# UART-to-ESP32-WROOM_with_JTAG.net
KiCad netlist of a schematic drawn in EAGLE
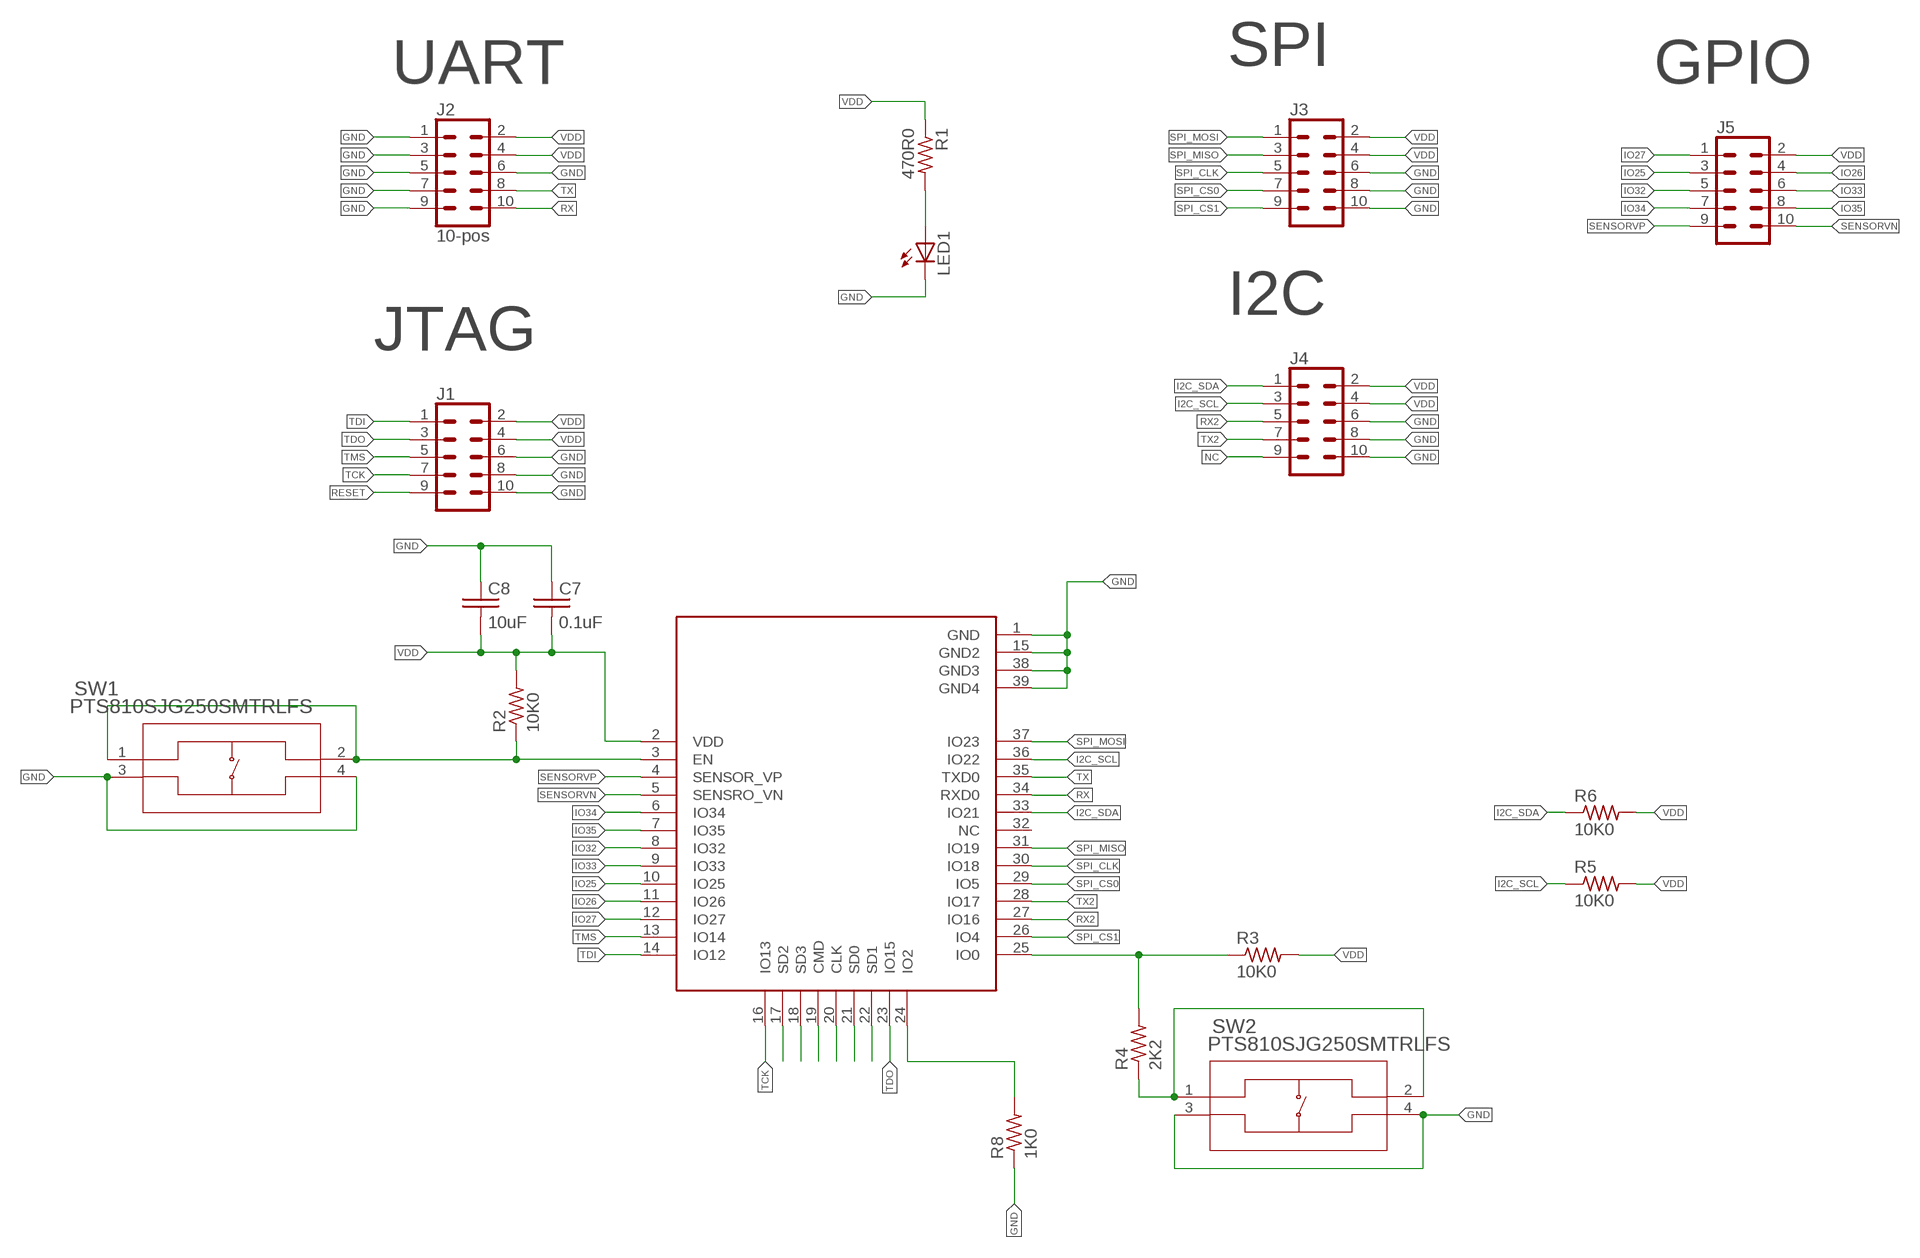
[diagram p0: schematic, sheet 1]

(export (version "E")
  (design (tool "Eeschema 10.0.6"))
  (components
    (comp (ref "C7")
      (value "0.1uF")
      (footprint "eagle-import:0402")
      (fields (field (name "PARTNO") "CL05F104ZO5NNNC"))
      (libsource (lib "eagle-import") (part "C_0402_0.1UF"))
    )
    (comp (ref "C8")
      (value "10uF")
      (footprint "eagle-import:0402")
      (fields (field (name "PARTNO") "CL05A106MP8NUB8"))
      (libsource (lib "eagle-import") (part "C_0402_10UF"))
    )
    (comp (ref "J1")
      (value "CONN_05X2PTH")
      (footprint "eagle-import:2X5")
      (libsource (lib "eagle-import") (part "CONN_05X2PTH"))
    )
    (comp (ref "J2")
      (value "10-pos")
      (footprint "eagle-import:2X5@1")
      (fields (field (name "PARTNO") "PH2RA-10-UA"))
      (libsource (lib "eagle-import") (part "CONN_05X2_RAPTH"))
    )
    (comp (ref "J3")
      (value "CONN_05X2PTH")
      (footprint "eagle-import:2X5")
      (libsource (lib "eagle-import") (part "CONN_05X2PTH"))
    )
    (comp (ref "J4")
      (value "CONN_05X2PTH")
      (footprint "eagle-import:2X5")
      (libsource (lib "eagle-import") (part "CONN_05X2PTH"))
    )
    (comp (ref "J5")
      (value "CONN_05X2PTH")
      (footprint "eagle-import:2X5")
      (libsource (lib "eagle-import") (part "CONN_05X2PTH"))
    )
    (comp (ref "LED1")
      (value "Green")
      (footprint "eagle-import:LED_0805_GREEN")
      (fields (field (name "PARTNO") "LG R971-KN-1"))
      (libsource (lib "eagle-import") (part "LED_0805_GREEN"))
    )
    (comp (ref "R1")
      (value "470R0")
      (footprint "eagle-import:0402")
      (fields (field (name "PARTNO") "RMCF0402JT470R"))
      (libsource (lib "eagle-import") (part "R_0402_470R0"))
    )
    (comp (ref "R2")
      (value "10K0")
      (footprint "eagle-import:0402")
      (fields (field (name "PARTNO") "RMCF0402JT10K0"))
      (libsource (lib "eagle-import") (part "R_0402_10K0"))
    )
    (comp (ref "R3")
      (value "10K0")
      (footprint "eagle-import:0402")
      (fields (field (name "PARTNO") "RMCF0402JT10K0"))
      (libsource (lib "eagle-import") (part "R_0402_10K0"))
    )
    (comp (ref "R4")
      (value "2K2")
      (footprint "eagle-import:0402")
      (fields (field (name "PARTNO") "RMCF0402JT2K20"))
      (libsource (lib "eagle-import") (part "R_0402_2K2"))
    )
    (comp (ref "R5")
      (value "10K0")
      (footprint "eagle-import:0402")
      (fields (field (name "PARTNO") "RMCF0402JT10K0"))
      (libsource (lib "eagle-import") (part "R_0402_10K0"))
    )
    (comp (ref "R6")
      (value "10K0")
      (footprint "eagle-import:0402")
      (fields (field (name "PARTNO") "RMCF0402JT10K0"))
      (libsource (lib "eagle-import") (part "R_0402_10K0"))
    )
    (comp (ref "R8")
      (value "1K0")
      (footprint "eagle-import:0402")
      (fields (field (name "PARTNO") "CRG0402J1K0"))
      (libsource (lib "eagle-import") (part "R_0402_1K0"))
    )
    (comp (ref "SW1")
      (value "PTS810SJG250SMTRLFS")
      (footprint "eagle-import:PTS810")
      (fields (field (name "COPYRIGHT") "Copyright (C) 2018 Accelerated Designs. All rights reserved"))
      (libsource (lib "eagle-import") (part "PTS810SJG250SMTRLFS"))
    )
    (comp (ref "SW2")
      (value "PTS810SJG250SMTRLFS")
      (footprint "eagle-import:PTS810")
      (fields (field (name "COPYRIGHT") "Copyright (C) 2018 Accelerated Designs. All rights reserved"))
      (libsource (lib "eagle-import") (part "PTS810SJG250SMTRLFS"))
    )
    (comp (ref "U2")
      (value "ESP32-WROOM-32D")
      (footprint "eagle-import:ESP32-WROOM-32D")
      (libsource (lib "eagle-import") (part "ESP32-WROOM-32D"))
    )
  )
  (nets
    (net (code "1") (name "GND") (class "Default")
      (node (ref "C7") (pin "P$1") (pinfunction "1_P$1") (pintype "passive"))
      (node (ref "C8") (pin "P$1") (pinfunction "1_P$1") (pintype "passive"))
      (node (ref "J1") (pin "10") (pinfunction "10_10") (pintype "passive"))
      (node (ref "J1") (pin "6") (pinfunction "6_6") (pintype "passive"))
      (node (ref "J1") (pin "8") (pinfunction "8_8") (pintype "passive"))
      (node (ref "J2") (pin "1") (pinfunction "1_1") (pintype "passive"))
      (node (ref "J2") (pin "3") (pinfunction "3_3") (pintype "passive"))
      (node (ref "J2") (pin "5") (pinfunction "5_5") (pintype "passive"))
      (node (ref "J2") (pin "6") (pinfunction "6_6") (pintype "passive"))
      (node (ref "J2") (pin "7") (pinfunction "7_7") (pintype "passive"))
      (node (ref "J2") (pin "9") (pinfunction "9_9") (pintype "passive"))
      (node (ref "J3") (pin "10") (pinfunction "10_10") (pintype "passive"))
      (node (ref "J3") (pin "6") (pinfunction "6_6") (pintype "passive"))
      (node (ref "J3") (pin "8") (pinfunction "8_8") (pintype "passive"))
      (node (ref "J4") (pin "10") (pinfunction "10_10") (pintype "passive"))
      (node (ref "J4") (pin "6") (pinfunction "6_6") (pintype "passive"))
      (node (ref "J4") (pin "8") (pinfunction "8_8") (pintype "passive"))
      (node (ref "LED1") (pin "C") (pinfunction "C_C") (pintype "passive"))
      (node (ref "R8") (pin "P$1") (pinfunction "1_P$1") (pintype "passive"))
      (node (ref "SW1") (pin "3") (pinfunction "3_3") (pintype "passive"))
      (node (ref "SW1") (pin "4") (pinfunction "4_4") (pintype "passive"))
      (node (ref "SW2") (pin "3") (pinfunction "3_3") (pintype "passive"))
      (node (ref "SW2") (pin "4") (pinfunction "4_4") (pintype "passive"))
      (node (ref "U2") (pin "1") (pinfunction "GND_1") (pintype "bidirectional"))
      (node (ref "U2") (pin "15") (pinfunction "GND2_15") (pintype "bidirectional"))
      (node (ref "U2") (pin "38") (pinfunction "GND3_38") (pintype "bidirectional"))
      (node (ref "U2") (pin "39") (pinfunction "GND4_39") (pintype "bidirectional"))
    )
    (net (code "2") (name "I2C_SCL") (class "Default")
      (node (ref "J4") (pin "3") (pinfunction "3_3") (pintype "passive"))
      (node (ref "R5") (pin "P$1") (pinfunction "1_P$1") (pintype "passive"))
      (node (ref "U2") (pin "36") (pinfunction "IO22_36") (pintype "bidirectional"))
    )
    (net (code "3") (name "I2C_SDA") (class "Default")
      (node (ref "J4") (pin "1") (pinfunction "1_1") (pintype "passive"))
      (node (ref "R6") (pin "P$1") (pinfunction "1_P$1") (pintype "passive"))
      (node (ref "U2") (pin "33") (pinfunction "IO21_33") (pintype "bidirectional"))
    )
    (net (code "4") (name "IO25") (class "Default")
      (node (ref "J5") (pin "3") (pinfunction "3_3") (pintype "passive"))
      (node (ref "U2") (pin "10") (pinfunction "IO25_10") (pintype "bidirectional"))
    )
    (net (code "5") (name "IO26") (class "Default")
      (node (ref "J5") (pin "4") (pinfunction "4_4") (pintype "passive"))
      (node (ref "U2") (pin "11") (pinfunction "IO26_11") (pintype "bidirectional"))
    )
    (net (code "6") (name "IO27") (class "Default")
      (node (ref "J5") (pin "1") (pinfunction "1_1") (pintype "passive"))
      (node (ref "U2") (pin "12") (pinfunction "IO27_12") (pintype "bidirectional"))
    )
    (net (code "7") (name "IO32") (class "Default")
      (node (ref "J5") (pin "5") (pinfunction "5_5") (pintype "passive"))
      (node (ref "U2") (pin "8") (pinfunction "IO32_8") (pintype "bidirectional"))
    )
    (net (code "8") (name "IO33") (class "Default")
      (node (ref "J5") (pin "6") (pinfunction "6_6") (pintype "passive"))
      (node (ref "U2") (pin "9") (pinfunction "IO33_9") (pintype "bidirectional"))
    )
    (net (code "9") (name "IO34") (class "Default")
      (node (ref "J5") (pin "7") (pinfunction "7_7") (pintype "passive"))
      (node (ref "U2") (pin "6") (pinfunction "IO34_6") (pintype "bidirectional"))
    )
    (net (code "10") (name "IO35") (class "Default")
      (node (ref "J5") (pin "8") (pinfunction "8_8") (pintype "passive"))
      (node (ref "U2") (pin "7") (pinfunction "IO35_7") (pintype "bidirectional"))
    )
    (net (code "11") (name "NC") (class "Default")
      (node (ref "J4") (pin "9") (pinfunction "9_9") (pintype "passive"))
    )
    (net (code "12") (name "Net-(R1-2)") (class "Default")
      (node (ref "LED1") (pin "A") (pinfunction "A_A") (pintype "passive"))
      (node (ref "R1") (pin "P$2") (pinfunction "2_P$2") (pintype "passive"))
    )
    (net (code "13") (name "Net-(R2-1)") (class "Default")
      (node (ref "R2") (pin "P$1") (pinfunction "1_P$1") (pintype "passive"))
      (node (ref "SW1") (pin "1") (pinfunction "1_1") (pintype "passive"))
      (node (ref "SW1") (pin "2") (pinfunction "2_2") (pintype "passive"))
      (node (ref "U2") (pin "3") (pinfunction "EN_3") (pintype "bidirectional"))
    )
    (net (code "14") (name "Net-(R3-1)") (class "Default")
      (node (ref "R3") (pin "P$1") (pinfunction "1_P$1") (pintype "passive"))
      (node (ref "R4") (pin "P$2") (pinfunction "2_P$2") (pintype "passive"))
      (node (ref "U2") (pin "25") (pinfunction "IO0_25") (pintype "bidirectional"))
    )
    (net (code "15") (name "Net-(R4-1)") (class "Default")
      (node (ref "R4") (pin "P$1") (pinfunction "1_P$1") (pintype "passive"))
      (node (ref "SW2") (pin "1") (pinfunction "1_1") (pintype "passive"))
      (node (ref "SW2") (pin "2") (pinfunction "2_2") (pintype "passive"))
    )
    (net (code "16") (name "Net-(R8-2)") (class "Default")
      (node (ref "R8") (pin "P$2") (pinfunction "2_P$2") (pintype "passive"))
      (node (ref "U2") (pin "24") (pinfunction "IO2_24") (pintype "bidirectional"))
    )
    (net (code "17") (name "RESET") (class "Default")
      (node (ref "J1") (pin "9") (pinfunction "9_9") (pintype "passive"))
    )
    (net (code "18") (name "RX") (class "Default")
      (node (ref "J2") (pin "10") (pinfunction "10_10") (pintype "passive"))
      (node (ref "U2") (pin "34") (pinfunction "RXD0_34") (pintype "bidirectional"))
    )
    (net (code "19") (name "RX2") (class "Default")
      (node (ref "J4") (pin "5") (pinfunction "5_5") (pintype "passive"))
      (node (ref "U2") (pin "27") (pinfunction "IO16_27") (pintype "bidirectional"))
    )
    (net (code "20") (name "SENSORVN") (class "Default")
      (node (ref "J5") (pin "10") (pinfunction "10_10") (pintype "passive"))
      (node (ref "U2") (pin "5") (pinfunction "SENSRO_VN_5") (pintype "bidirectional"))
    )
    (net (code "21") (name "SENSORVP") (class "Default")
      (node (ref "J5") (pin "9") (pinfunction "9_9") (pintype "passive"))
      (node (ref "U2") (pin "4") (pinfunction "SENSOR_VP_4") (pintype "bidirectional"))
    )
    (net (code "22") (name "SPI_CLK") (class "Default")
      (node (ref "J3") (pin "5") (pinfunction "5_5") (pintype "passive"))
      (node (ref "U2") (pin "30") (pinfunction "IO18_30") (pintype "bidirectional"))
    )
    (net (code "23") (name "SPI_CS0") (class "Default")
      (node (ref "J3") (pin "7") (pinfunction "7_7") (pintype "passive"))
      (node (ref "U2") (pin "29") (pinfunction "IO5_29") (pintype "bidirectional"))
    )
    (net (code "24") (name "SPI_CS1") (class "Default")
      (node (ref "J3") (pin "9") (pinfunction "9_9") (pintype "passive"))
      (node (ref "U2") (pin "26") (pinfunction "IO4_26") (pintype "bidirectional"))
    )
    (net (code "25") (name "SPI_MISO") (class "Default")
      (node (ref "J3") (pin "3") (pinfunction "3_3") (pintype "passive"))
      (node (ref "U2") (pin "31") (pinfunction "IO19_31") (pintype "bidirectional"))
    )
    (net (code "26") (name "SPI_MOSI") (class "Default")
      (node (ref "J3") (pin "1") (pinfunction "1_1") (pintype "passive"))
      (node (ref "U2") (pin "37") (pinfunction "IO23_37") (pintype "bidirectional"))
    )
    (net (code "27") (name "TCK") (class "Default")
      (node (ref "J1") (pin "7") (pinfunction "7_7") (pintype "passive"))
      (node (ref "U2") (pin "16") (pinfunction "IO13_16") (pintype "bidirectional"))
    )
    (net (code "28") (name "TDI") (class "Default")
      (node (ref "J1") (pin "1") (pinfunction "1_1") (pintype "passive"))
      (node (ref "U2") (pin "14") (pinfunction "IO12_14") (pintype "bidirectional"))
    )
    (net (code "29") (name "TDO") (class "Default")
      (node (ref "J1") (pin "3") (pinfunction "3_3") (pintype "passive"))
      (node (ref "U2") (pin "23") (pinfunction "IO15_23") (pintype "bidirectional"))
    )
    (net (code "30") (name "TMS") (class "Default")
      (node (ref "J1") (pin "5") (pinfunction "5_5") (pintype "passive"))
      (node (ref "U2") (pin "13") (pinfunction "IO14_13") (pintype "bidirectional"))
    )
    (net (code "31") (name "TX") (class "Default")
      (node (ref "J2") (pin "8") (pinfunction "8_8") (pintype "passive"))
      (node (ref "U2") (pin "35") (pinfunction "TXD0_35") (pintype "bidirectional"))
    )
    (net (code "32") (name "TX2") (class "Default")
      (node (ref "J4") (pin "7") (pinfunction "7_7") (pintype "passive"))
      (node (ref "U2") (pin "28") (pinfunction "IO17_28") (pintype "bidirectional"))
    )
    (net (code "33") (name "VDD") (class "Default")
      (node (ref "C7") (pin "P$2") (pinfunction "2_P$2") (pintype "passive"))
      (node (ref "C8") (pin "P$2") (pinfunction "2_P$2") (pintype "passive"))
      (node (ref "J1") (pin "2") (pinfunction "2_2") (pintype "passive"))
      (node (ref "J1") (pin "4") (pinfunction "4_4") (pintype "passive"))
      (node (ref "J2") (pin "2") (pinfunction "2_2") (pintype "passive"))
      (node (ref "J2") (pin "4") (pinfunction "4_4") (pintype "passive"))
      (node (ref "J3") (pin "2") (pinfunction "2_2") (pintype "passive"))
      (node (ref "J3") (pin "4") (pinfunction "4_4") (pintype "passive"))
      (node (ref "J4") (pin "2") (pinfunction "2_2") (pintype "passive"))
      (node (ref "J4") (pin "4") (pinfunction "4_4") (pintype "passive"))
      (node (ref "J5") (pin "2") (pinfunction "2_2") (pintype "passive"))
      (node (ref "R1") (pin "P$1") (pinfunction "1_P$1") (pintype "passive"))
      (node (ref "R2") (pin "P$2") (pinfunction "2_P$2") (pintype "passive"))
      (node (ref "R3") (pin "P$2") (pinfunction "2_P$2") (pintype "passive"))
      (node (ref "R5") (pin "P$2") (pinfunction "2_P$2") (pintype "passive"))
      (node (ref "R6") (pin "P$2") (pinfunction "2_P$2") (pintype "passive"))
      (node (ref "U2") (pin "2") (pinfunction "VDD_2") (pintype "bidirectional"))
    )
    (net (code "34") (name "unconnected-(U2-CLK-Pad20)") (class "Default")
      (node (ref "U2") (pin "20") (pinfunction "CLK_20") (pintype "bidirectional"))
    )
    (net (code "35") (name "unconnected-(U2-CMD-Pad19)") (class "Default")
      (node (ref "U2") (pin "19") (pinfunction "CMD_19") (pintype "bidirectional"))
    )
    (net (code "36") (name "unconnected-(U2-NC-Pad32)") (class "Default")
      (node (ref "U2") (pin "32") (pinfunction "NC_32") (pintype "bidirectional"))
    )
    (net (code "37") (name "unconnected-(U2-SD0-Pad21)") (class "Default")
      (node (ref "U2") (pin "21") (pinfunction "SD0_21") (pintype "bidirectional"))
    )
    (net (code "38") (name "unconnected-(U2-SD1-Pad22)") (class "Default")
      (node (ref "U2") (pin "22") (pinfunction "SD1_22") (pintype "bidirectional"))
    )
    (net (code "39") (name "unconnected-(U2-SD2-Pad17)") (class "Default")
      (node (ref "U2") (pin "17") (pinfunction "SD2_17") (pintype "bidirectional"))
    )
    (net (code "40") (name "unconnected-(U2-SD3-Pad18)") (class "Default")
      (node (ref "U2") (pin "18") (pinfunction "SD3_18") (pintype "bidirectional"))
    )
  )
)
